# offzone-addon-s7-easyeda.net
KiCad netlist of a schematic drawn in EasyEDA
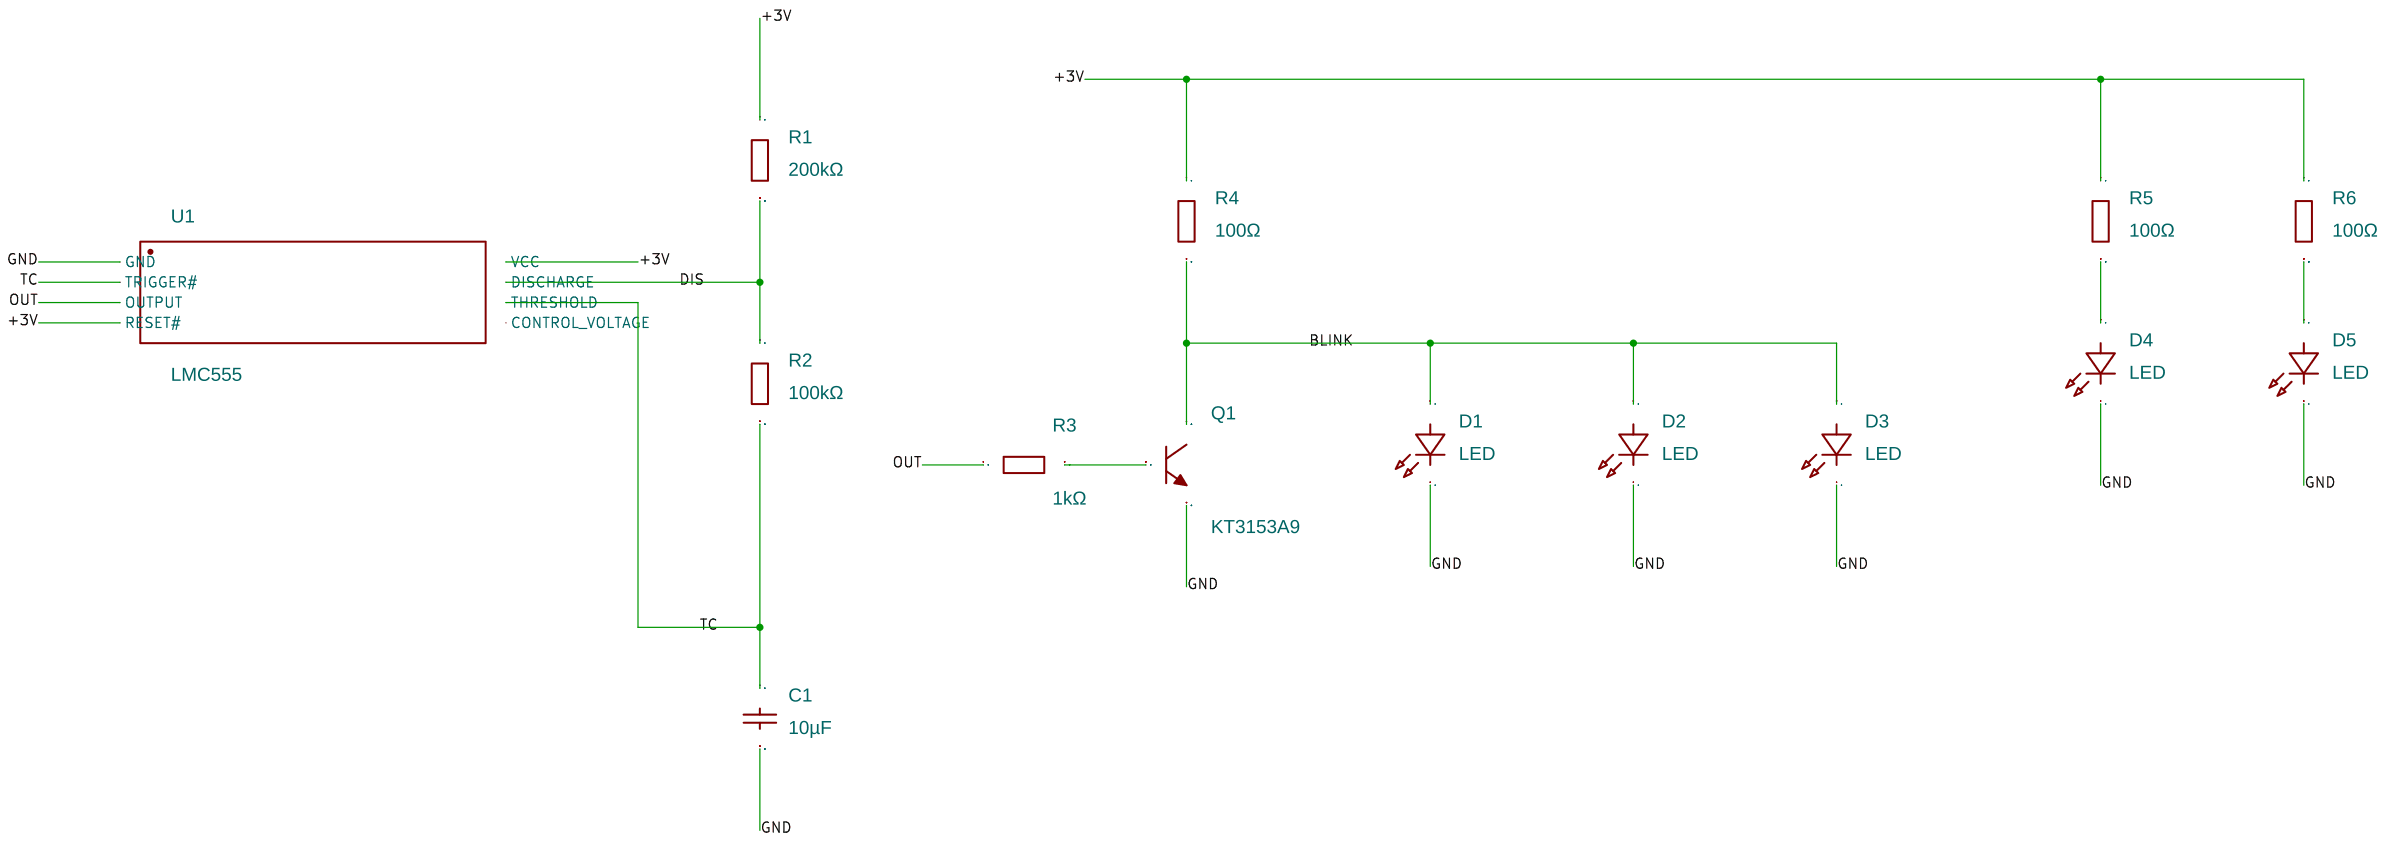
[diagram p0: schematic sheet]

(export (version "E")
  (design (tool "Eeschema 10.0.6"))
  (components
    (comp (ref "C1")
      (value "10µF")
      (fields
        (field (name "BOM_Manufacturer Part") "CL21A106KOQNNNE")
        (field (name "BOM_Supplier Part") "C1713")
      )
      (libsource (lib "") (part "CL21A106KOQNNNE"))
    )
    (comp (ref "D1")
      (value "LED")
      (fields
        (field (name "BOM_Manufacturer Part") "17-21/R6C-AQ2R2B/4T")
        (field (name "BOM_Supplier Part") "C2971979")
      )
      (libsource (lib "") (part "17-21/R6C-AQ2R2B/4T"))
    )
    (comp (ref "D2")
      (value "LED")
      (fields
        (field (name "BOM_Manufacturer Part") "17-21/R6C-AQ2R2B/4T")
        (field (name "BOM_Supplier Part") "C2971979")
      )
      (libsource (lib "") (part "17-21/R6C-AQ2R2B/4T"))
    )
    (comp (ref "D3")
      (value "LED")
      (fields
        (field (name "BOM_Manufacturer Part") "17-21/R6C-AQ2R2B/4T")
        (field (name "BOM_Supplier Part") "C2971979")
      )
      (libsource (lib "") (part "17-21/R6C-AQ2R2B/4T"))
    )
    (comp (ref "D4")
      (value "LED")
      (fields
        (field (name "BOM_Manufacturer Part") "17-21/R6C-AQ2R2B/4T")
        (field (name "BOM_Supplier Part") "C2971979")
      )
      (libsource (lib "") (part "17-21/R6C-AQ2R2B/4T"))
    )
    (comp (ref "D5")
      (value "LED")
      (fields
        (field (name "BOM_Manufacturer Part") "17-21/R6C-AQ2R2B/4T")
        (field (name "BOM_Supplier Part") "C2971979")
      )
      (libsource (lib "") (part "17-21/R6C-AQ2R2B/4T"))
    )
    (comp (ref "Q1")
      (value "KT3153A9")
      (fields (field (name "BOM_Manufacturer Part") "КТ3153А9"))
      (libsource (lib "") (part "KT3153A9"))
    )
    (comp (ref "R1")
      (value "200kΩ")
      (fields
        (field (name "BOM_Manufacturer Part") "0603WAF2003T5E")
        (field (name "BOM_Supplier Part") "C25811")
      )
      (libsource (lib "") (part "0603WAF2003T5E"))
    )
    (comp (ref "R2")
      (value "100kΩ")
      (fields
        (field (name "BOM_Manufacturer Part") "0603WAF1003T5E")
        (field (name "BOM_Supplier Part") "C25803")
      )
      (libsource (lib "") (part "0603WAF1003T5E"))
    )
    (comp (ref "R3")
      (value "1kΩ")
      (fields
        (field (name "BOM_Manufacturer Part") "0603WAF1001T5E")
        (field (name "BOM_Supplier Part") "C21190")
      )
      (libsource (lib "") (part "0603WAF1001T5E"))
    )
    (comp (ref "R4")
      (value "100Ω")
      (fields
        (field (name "BOM_Manufacturer Part") "RC0603FR-07100RL")
        (field (name "BOM_Supplier Part") "C105588")
      )
      (libsource (lib "") (part "RC0603FR-07100RL"))
    )
    (comp (ref "R5")
      (value "100Ω")
      (fields
        (field (name "BOM_Manufacturer Part") "RC0603FR-07100RL")
        (field (name "BOM_Supplier Part") "C105588")
      )
      (libsource (lib "") (part "RC0603FR-07100RL"))
    )
    (comp (ref "R6")
      (value "100Ω")
      (fields
        (field (name "BOM_Manufacturer Part") "RC0603FR-07100RL")
        (field (name "BOM_Supplier Part") "C105588")
      )
      (libsource (lib "") (part "RC0603FR-07100RL"))
    )
    (comp (ref "U1")
      (value "LMC555")
      (fields
        (field (name "BOM_Manufacturer Part") "LMC555M/TR")
        (field (name "BOM_Supplier Part") "C356725")
      )
      (libsource (lib "") (part "LMC555M/TR"))
    )
  )
  (nets
    (net (code "1") (name "/+3V") (class "Default")
      (node (ref "R1") (pin "1") (pinfunction "1_1") (pintype "input"))
      (node (ref "R4") (pin "1") (pinfunction "1_1") (pintype "input"))
      (node (ref "R5") (pin "1") (pinfunction "1_1") (pintype "input"))
      (node (ref "R6") (pin "1") (pinfunction "1_1") (pintype "input"))
      (node (ref "U1") (pin "4") (pinfunction "RESET#_4") (pintype "unspecified"))
      (node (ref "U1") (pin "8") (pinfunction "VCC_8") (pintype "unspecified"))
    )
    (net (code "2") (name "/BLINK") (class "Default")
      (node (ref "D1") (pin "2") (pinfunction "A_2") (pintype "unspecified"))
      (node (ref "D2") (pin "2") (pinfunction "A_2") (pintype "unspecified"))
      (node (ref "D3") (pin "2") (pinfunction "A_2") (pintype "unspecified"))
      (node (ref "Q1") (pin "1") (pinfunction "3_1") (pintype "input"))
      (node (ref "R4") (pin "2") (pinfunction "2_2") (pintype "input"))
    )
    (net (code "3") (name "/DIS") (class "Default")
      (node (ref "R1") (pin "2") (pinfunction "2_2") (pintype "input"))
      (node (ref "R2") (pin "1") (pinfunction "1_1") (pintype "input"))
      (node (ref "U1") (pin "7") (pinfunction "DISCHARGE_7") (pintype "unspecified"))
    )
    (net (code "4") (name "/GND") (class "Default")
      (node (ref "C1") (pin "2") (pinfunction "2_2") (pintype "input"))
      (node (ref "D1") (pin "1") (pinfunction "K_1") (pintype "unspecified"))
      (node (ref "D2") (pin "1") (pinfunction "K_1") (pintype "unspecified"))
      (node (ref "D3") (pin "1") (pinfunction "K_1") (pintype "unspecified"))
      (node (ref "D4") (pin "1") (pinfunction "K_1") (pintype "unspecified"))
      (node (ref "D5") (pin "1") (pinfunction "K_1") (pintype "unspecified"))
      (node (ref "Q1") (pin "3") (pinfunction "2_3") (pintype "input"))
      (node (ref "U1") (pin "1") (pinfunction "GND_1") (pintype "unspecified"))
    )
    (net (code "5") (name "/OUT") (class "Default")
      (node (ref "R3") (pin "1") (pinfunction "1_1") (pintype "input"))
      (node (ref "U1") (pin "3") (pinfunction "OUTPUT_3") (pintype "unspecified"))
    )
    (net (code "6") (name "/TC") (class "Default")
      (node (ref "C1") (pin "1") (pinfunction "1_1") (pintype "input"))
      (node (ref "R2") (pin "2") (pinfunction "2_2") (pintype "input"))
      (node (ref "U1") (pin "2") (pinfunction "TRIGGER#_2") (pintype "unspecified"))
      (node (ref "U1") (pin "6") (pinfunction "THRESHOLD_6") (pintype "unspecified"))
    )
    (net (code "7") (name "Net-(D4-A)") (class "Default")
      (node (ref "D4") (pin "2") (pinfunction "A_2") (pintype "unspecified"))
      (node (ref "R5") (pin "2") (pinfunction "2_2") (pintype "input"))
    )
    (net (code "8") (name "Net-(D5-A)") (class "Default")
      (node (ref "D5") (pin "2") (pinfunction "A_2") (pintype "unspecified"))
      (node (ref "R6") (pin "2") (pinfunction "2_2") (pintype "input"))
    )
    (net (code "9") (name "Net-(Q1-1)") (class "Default")
      (node (ref "Q1") (pin "2") (pinfunction "1_2") (pintype "input"))
      (node (ref "R3") (pin "2") (pinfunction "2_2") (pintype "input"))
    )
    (net (code "10") (name "unconnected-(U1-CONTROL_VOLTAGE-Pad5)") (class "Default")
      (node (ref "U1") (pin "5") (pinfunction "CONTROL_VOLTAGE_5") (pintype "unspecified"))
    )
  )
)
